# Sheet1.net
KiCad netlist of a schematic drawn in Altium Designer
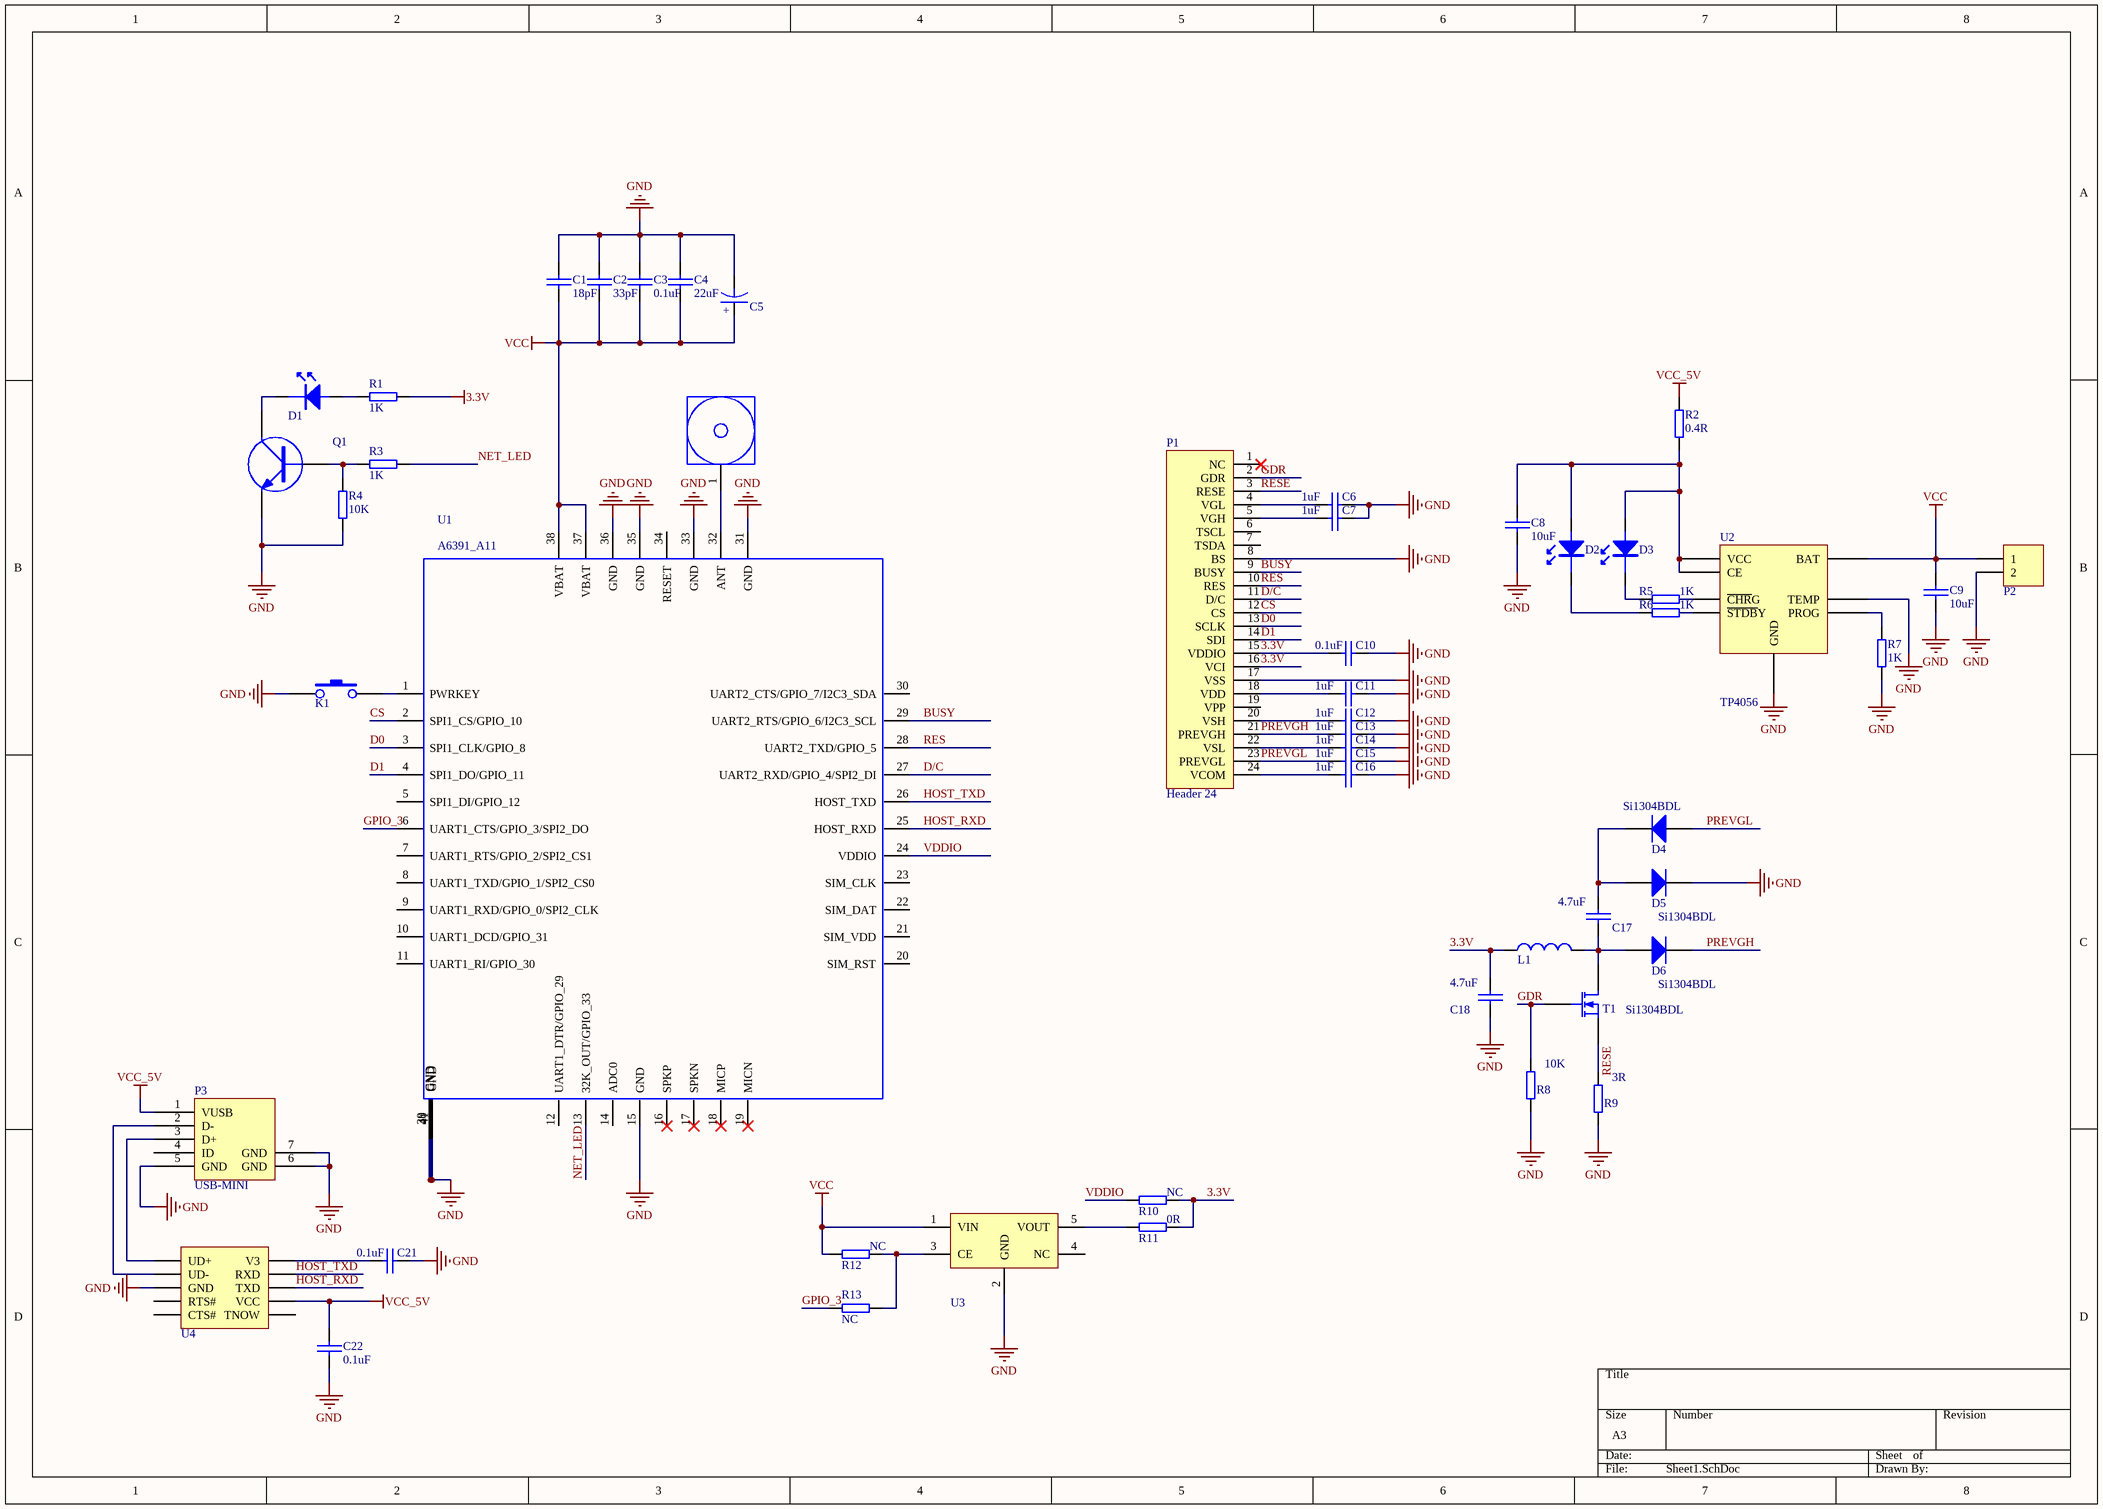
[diagram p0: Sheet1.SchDoc]

(export (version "E")
  (design (tool "Eeschema 10.0.6"))
  (components
    (comp (ref "ANTENNA")
      (value "ANTENNA")
      (footprint "GSM/GPRS/3G弹簧天线")
      (libsource (lib "Library") (part "ANTENNA"))
    )
    (comp (ref "C1")
      (value "18pF")
      (footprint "0603C-Cap")
      (description "ceramics")
      (libsource (lib "Library") (part "Cap"))
    )
    (comp (ref "C2")
      (value "33pF")
      (footprint "0603C-Cap")
      (description "ceramics")
      (libsource (lib "Library") (part "Cap"))
    )
    (comp (ref "C3")
      (value "0.1uF")
      (footprint "0603C-Cap")
      (description "ceramics")
      (libsource (lib "Library") (part "Cap"))
    )
    (comp (ref "C4")
      (value "22uF")
      (footprint "0603C-Cap")
      (description "ceramics")
      (libsource (lib "Library") (part "Cap"))
    )
    (comp (ref "C5")
      (value "Cap_C")
      (footprint "CAPM-B-3528X21N")
      (description "Electrolytic")
      (libsource (lib "Library") (part "Cap_C"))
    )
    (comp (ref "C6")
      (value "1uF")
      (footprint "0603C-Cap")
      (description "ceramics")
      (libsource (lib "Library") (part "Cap"))
    )
    (comp (ref "C7")
      (value "1uF")
      (footprint "0603C-Cap")
      (description "ceramics")
      (libsource (lib "Library") (part "Cap"))
    )
    (comp (ref "C8")
      (value "10uF")
      (footprint "0603C-Cap")
      (description "ceramics")
      (libsource (lib "Library") (part "Cap"))
    )
    (comp (ref "C9")
      (value "10uF")
      (footprint "0603C-Cap")
      (description "ceramics")
      (libsource (lib "Library") (part "Cap"))
    )
    (comp (ref "C10")
      (value "0.1uF")
      (footprint "0603C-Cap")
      (description "ceramics")
      (libsource (lib "Library") (part "Cap"))
    )
    (comp (ref "C11")
      (value "1uF")
      (footprint "0603C-Cap")
      (description "ceramics")
      (libsource (lib "Library") (part "Cap"))
    )
    (comp (ref "C12")
      (value "1uF")
      (footprint "0603C-Cap")
      (description "ceramics")
      (libsource (lib "Library") (part "Cap"))
    )
    (comp (ref "C13")
      (value "1uF")
      (footprint "0603C-Cap")
      (description "ceramics")
      (libsource (lib "Library") (part "Cap"))
    )
    (comp (ref "C14")
      (value "1uF")
      (footprint "0603C-Cap")
      (description "ceramics")
      (libsource (lib "Library") (part "Cap"))
    )
    (comp (ref "C15")
      (value "1uF")
      (footprint "0603C-Cap")
      (description "ceramics")
      (libsource (lib "Library") (part "Cap"))
    )
    (comp (ref "C16")
      (value "1uF")
      (footprint "0603C-Cap")
      (description "ceramics")
      (libsource (lib "Library") (part "Cap"))
    )
    (comp (ref "C17")
      (value "4.7uF")
      (footprint "0603C-Cap")
      (description "ceramics")
      (libsource (lib "Library") (part "Cap"))
    )
    (comp (ref "C18")
      (value "4.7uF")
      (footprint "0603C-Cap")
      (description "ceramics")
      (libsource (lib "Library") (part "Cap"))
    )
    (comp (ref "C21")
      (value "0.1uF")
      (footprint "0603C-Cap")
      (description "ceramics")
      (libsource (lib "Library") (part "Cap"))
    )
    (comp (ref "C22")
      (value "0.1uF")
      (footprint "0603C-Cap")
      (description "ceramics")
      (libsource (lib "Library") (part "Cap"))
    )
    (comp (ref "D1")
      (value "LED")
      (footprint "LED0603_B")
      (description "发光二极管")
      (libsource (lib "Library") (part "LED"))
    )
    (comp (ref "D2")
      (value "LED")
      (footprint "LED0603_B")
      (description "发光二极管")
      (libsource (lib "Library") (part "LED"))
    )
    (comp (ref "D3")
      (value "LED")
      (footprint "LED0603_B")
      (description "发光二极管")
      (libsource (lib "Library") (part "LED"))
    )
    (comp (ref "D4")
      (value "Si1304BDL")
      (footprint "SOD323")
      (libsource (lib "Library") (part "Diode BAS16"))
    )
    (comp (ref "D5")
      (value "Si1304BDL")
      (footprint "SOD323")
      (libsource (lib "Library") (part "Diode BAS16"))
    )
    (comp (ref "D6")
      (value "Si1304BDL")
      (footprint "SOD323")
      (libsource (lib "Library") (part "Diode BAS16"))
    )
    (comp (ref "K1") (value "SW_PB2") (footprint "KEY_4*4") (libsource (lib "Library") (part "SW_PB2")))
    (comp (ref "L1")
      (value "10uH")
      (footprint "3225 - duplicate")
      (description "INDUCTOR")
      (libsource (lib "Library") (part "Inductor"))
    )
    (comp (ref "P1")
      (value "Header 24")
      (footprint "FH12-24S-0.5SH")
      (description "Header, 7-Pin")
      (libsource (lib "Library") (part "Header 24"))
    )
    (comp (ref "P2") (value "Header 2") (footprint "2PIN") (libsource (lib "Library") (part "Header 2")))
    (comp (ref "P3")
      (value "USB-MINI")
      (footprint "Micro USB")
      (description "MINUSB")
      (libsource (lib "Library") (part "USB-MINI"))
    )
    (comp (ref "Q1")
      (value "8050")
      (footprint "SOT-23")
      (description "NPN")
      (libsource (lib "Library") (part "NPN"))
    )
    (comp (ref "R1")
      (value "1K")
      (footprint "0603C-Res")
      (description "电阻")
      (libsource (lib "Library") (part "RES"))
    )
    (comp (ref "R2")
      (value "0.4R")
      (footprint "0603C-Res")
      (description "电阻")
      (libsource (lib "Library") (part "RES"))
    )
    (comp (ref "R3")
      (value "1K")
      (footprint "0603C-Res")
      (description "电阻")
      (libsource (lib "Library") (part "RES"))
    )
    (comp (ref "R4")
      (value "10K")
      (footprint "0603C-Res")
      (description "电阻")
      (libsource (lib "Library") (part "RES"))
    )
    (comp (ref "R5")
      (value "1K")
      (footprint "0603C-Res")
      (description "电阻")
      (libsource (lib "Library") (part "RES"))
    )
    (comp (ref "R6")
      (value "1K")
      (footprint "0603C-Res")
      (description "电阻")
      (libsource (lib "Library") (part "RES"))
    )
    (comp (ref "R7")
      (value "1K")
      (footprint "0603C-Res")
      (description "电阻")
      (libsource (lib "Library") (part "RES"))
    )
    (comp (ref "R8")
      (value "10K")
      (footprint "0603C-Res")
      (description "电阻")
      (libsource (lib "Library") (part "RES"))
    )
    (comp (ref "R9")
      (value "3R")
      (footprint "0603C-Res")
      (description "电阻")
      (libsource (lib "Library") (part "RES"))
    )
    (comp (ref "R10")
      (value "NC")
      (footprint "0603C-Res")
      (description "电阻")
      (libsource (lib "Library") (part "RES"))
    )
    (comp (ref "R11")
      (value "0R")
      (footprint "0603C-Res")
      (description "电阻")
      (libsource (lib "Library") (part "RES"))
    )
    (comp (ref "R12")
      (value "NC")
      (footprint "0603C-Res")
      (description "电阻")
      (libsource (lib "Library") (part "RES"))
    )
    (comp (ref "R13")
      (value "NC")
      (footprint "0603C-Res")
      (description "电阻")
      (libsource (lib "Library") (part "RES"))
    )
    (comp (ref "T1") (value "Si1304BDL") (footprint "SOT-23") (libsource (lib "Library") (part "N_MOS")))
    (comp (ref "U1")
      (value "A6391_A11")
      (footprint "202")
      (description "202芯片")
      (libsource (lib "Library") (part "A6391_A11"))
    )
    (comp (ref "U2") (value "TP4056") (footprint "SOP8LM386") (libsource (lib "Library") (part "TP4056")))
    (comp (ref "U3")
      (value "ME6211C33")
      (footprint "SOT-23-5PIN")
      (libsource (lib "Library") (part "ME6211C33"))
    )
    (comp (ref "U4")
      (value "CH340E")
      (footprint "TSSOP50P490X110-10N")
      (libsource (lib "Library") (part "CH340E"))
    )
  )
  (nets
    (net (code "1") (name "/BUSY") (class "Default")
      (node (ref "P1") (pin "9") (pinfunction "BUSY_9") (pintype "passive"))
      (node (ref "U1") (pin "29") (pinfunction "UART2_RTS/GPIO_6/I2C3_SCL_29") (pintype "passive"))
    )
    (net (code "2") (name "/CS") (class "Default")
      (node (ref "P1") (pin "12") (pinfunction "CS_12") (pintype "passive"))
      (node (ref "U1") (pin "2") (pinfunction "SPI1_CS/GPIO_10_2") (pintype "passive"))
    )
    (net (code "3") (name "/D0") (class "Default")
      (node (ref "P1") (pin "13") (pinfunction "SCLK_13") (pintype "passive"))
      (node (ref "U1") (pin "3") (pinfunction "SPI1_CLK/GPIO_8_3") (pintype "passive"))
    )
    (net (code "4") (name "/D1") (class "Default")
      (node (ref "P1") (pin "14") (pinfunction "SDI_14") (pintype "passive"))
      (node (ref "U1") (pin "4") (pinfunction "SPI1_DO/GPIO_11_4") (pintype "passive"))
    )
    (net (code "5") (name "/D{slash}C") (class "Default")
      (node (ref "P1") (pin "11") (pinfunction "D/C_11") (pintype "passive"))
      (node (ref "U1") (pin "27") (pinfunction "UART2_RXD/GPIO_4/SPI2_DI_27") (pintype "passive"))
    )
    (net (code "6") (name "/GDR") (class "Default")
      (node (ref "P1") (pin "2") (pinfunction "GDR_2") (pintype "passive"))
      (node (ref "R8") (pin "2") (pinfunction "2_2") (pintype "passive"))
      (node (ref "T1") (pin "1") (pinfunction "G_1") (pintype "passive"))
    )
    (net (code "7") (name "/GPIO_3") (class "Default")
      (node (ref "R13") (pin "2") (pinfunction "2_2") (pintype "passive"))
      (node (ref "U1") (pin "6") (pinfunction "UART1_CTS/GPIO_3/SPI2_DO_6") (pintype "passive"))
    )
    (net (code "8") (name "/HOST_RXD") (class "Default")
      (node (ref "U1") (pin "25") (pinfunction "HOST_RXD_25") (pintype "passive"))
      (node (ref "U4") (pin "8") (pinfunction "TXD_8") (pintype "passive"))
    )
    (net (code "9") (name "/HOST_TXD") (class "Default")
      (node (ref "U1") (pin "26") (pinfunction "HOST_TXD_26") (pintype "passive"))
      (node (ref "U4") (pin "9") (pinfunction "RXD_9") (pintype "passive"))
    )
    (net (code "10") (name "/NET_LED") (class "Default")
      (node (ref "R3") (pin "1") (pinfunction "1_1") (pintype "passive"))
      (node (ref "U1") (pin "13") (pinfunction "32K_OUT/GPIO_33_13") (pintype "passive"))
    )
    (net (code "11") (name "/PREVGH") (class "Default")
      (node (ref "C13") (pin "2") (pinfunction "2_2") (pintype "passive"))
      (node (ref "D6") (pin "2") (pinfunction "K_2") (pintype "passive"))
      (node (ref "P1") (pin "21") (pinfunction "PREVGH_21") (pintype "passive"))
    )
    (net (code "12") (name "/PREVGL") (class "Default")
      (node (ref "C15") (pin "2") (pinfunction "2_2") (pintype "passive"))
      (node (ref "D4") (pin "1") (pinfunction "A_1") (pintype "passive"))
      (node (ref "P1") (pin "23") (pinfunction "PREVGL_23") (pintype "passive"))
    )
    (net (code "13") (name "/RES") (class "Default")
      (node (ref "P1") (pin "10") (pinfunction "RES_10") (pintype "passive"))
      (node (ref "U1") (pin "28") (pinfunction "UART2_TXD/GPIO_5_28") (pintype "passive"))
    )
    (net (code "14") (name "/RESE") (class "Default")
      (node (ref "P1") (pin "3") (pinfunction "RESE_3") (pintype "passive"))
      (node (ref "R9") (pin "2") (pinfunction "2_2") (pintype "passive"))
      (node (ref "T1") (pin "2") (pinfunction "S_2") (pintype "passive"))
    )
    (net (code "15") (name "/VDDIO") (class "Default")
      (node (ref "R10") (pin "1") (pinfunction "1_1") (pintype "passive"))
      (node (ref "U1") (pin "24") (pinfunction "VDDIO_24") (pintype "passive"))
    )
    (net (code "16") (name "3.3V") (class "Default")
      (node (ref "C10") (pin "2") (pinfunction "2_2") (pintype "passive"))
      (node (ref "C18") (pin "2") (pinfunction "2_2") (pintype "passive"))
      (node (ref "L1") (pin "1") (pinfunction "1_1") (pintype "passive"))
      (node (ref "P1") (pin "15") (pinfunction "VDDIO_15") (pintype "passive"))
      (node (ref "P1") (pin "16") (pinfunction "VCI_16") (pintype "passive"))
      (node (ref "R1") (pin "2") (pinfunction "2_2") (pintype "passive"))
      (node (ref "R10") (pin "2") (pinfunction "2_2") (pintype "passive"))
      (node (ref "R11") (pin "2") (pinfunction "2_2") (pintype "passive"))
    )
    (net (code "17") (name "GND") (class "Default")
      (node (ref "C1") (pin "1") (pinfunction "1_1") (pintype "passive"))
      (node (ref "C10") (pin "1") (pinfunction "1_1") (pintype "passive"))
      (node (ref "C11") (pin "1") (pinfunction "1_1") (pintype "passive"))
      (node (ref "C12") (pin "1") (pinfunction "1_1") (pintype "passive"))
      (node (ref "C13") (pin "1") (pinfunction "1_1") (pintype "passive"))
      (node (ref "C14") (pin "1") (pinfunction "1_1") (pintype "passive"))
      (node (ref "C15") (pin "1") (pinfunction "1_1") (pintype "passive"))
      (node (ref "C16") (pin "1") (pinfunction "1_1") (pintype "passive"))
      (node (ref "C18") (pin "1") (pinfunction "1_1") (pintype "passive"))
      (node (ref "C2") (pin "1") (pinfunction "1_1") (pintype "passive"))
      (node (ref "C21") (pin "1") (pinfunction "1_1") (pintype "passive"))
      (node (ref "C22") (pin "1") (pinfunction "1_1") (pintype "passive"))
      (node (ref "C3") (pin "1") (pinfunction "1_1") (pintype "passive"))
      (node (ref "C4") (pin "1") (pinfunction "1_1") (pintype "passive"))
      (node (ref "C5") (pin "2") (pinfunction "2_2") (pintype "passive"))
      (node (ref "C6") (pin "1") (pinfunction "1_1") (pintype "passive"))
      (node (ref "C7") (pin "1") (pinfunction "1_1") (pintype "passive"))
      (node (ref "C8") (pin "2") (pinfunction "2_2") (pintype "passive"))
      (node (ref "C9") (pin "2") (pinfunction "2_2") (pintype "passive"))
      (node (ref "D5") (pin "2") (pinfunction "K_2") (pintype "passive"))
      (node (ref "K1") (pin "1") (pinfunction "1_1") (pintype "passive"))
      (node (ref "P1") (pin "17") (pinfunction "VSS_17") (pintype "passive"))
      (node (ref "P1") (pin "8") (pinfunction "BS_8") (pintype "passive"))
      (node (ref "P2") (pin "2") (pinfunction "2_2") (pintype "passive"))
      (node (ref "P3") (pin "5") (pinfunction "GND_5") (pintype "passive"))
      (node (ref "P3") (pin "6") (pinfunction "GND_6") (pintype "passive"))
      (node (ref "P3") (pin "7") (pinfunction "GND_7") (pintype "passive"))
      (node (ref "Q1") (pin "2") (pinfunction "E_2") (pintype "passive"))
      (node (ref "R4") (pin "1") (pinfunction "1_1") (pintype "passive"))
      (node (ref "R7") (pin "2") (pinfunction "2_2") (pintype "passive"))
      (node (ref "R8") (pin "1") (pinfunction "1_1") (pintype "passive"))
      (node (ref "R9") (pin "1") (pinfunction "1_1") (pintype "passive"))
      (node (ref "U1") (pin "15") (pinfunction "GND_15") (pintype "passive"))
      (node (ref "U1") (pin "31") (pinfunction "GND_31") (pintype "passive"))
      (node (ref "U1") (pin "33") (pinfunction "GND_33") (pintype "passive"))
      (node (ref "U1") (pin "35") (pinfunction "GND_35") (pintype "passive"))
      (node (ref "U1") (pin "36") (pinfunction "GND_36") (pintype "passive"))
      (node (ref "U1") (pin "39") (pinfunction "GND_39") (pintype "power_in"))
      (node (ref "U1") (pin "40") (pinfunction "GND_40") (pintype "power_in"))
      (node (ref "U1") (pin "41") (pinfunction "GND_41") (pintype "power_in"))
      (node (ref "U2") (pin "1") (pinfunction "TEMP_1") (pintype "passive"))
      (node (ref "U2") (pin "3") (pinfunction "GND_3") (pintype "passive"))
      (node (ref "U3") (pin "2") (pinfunction "GND_2") (pintype "passive"))
      (node (ref "U4") (pin "3") (pinfunction "GND_3") (pintype "passive"))
    )
    (net (code "18") (name "Net-(D1-PadA)") (class "Default")
      (node (ref "D1") (pin "A") (pinfunction "A_A") (pintype "passive"))
      (node (ref "R1") (pin "1") (pinfunction "1_1") (pintype "passive"))
    )
    (net (code "19") (name "Net-(D2-PadK)") (class "Default")
      (node (ref "D2") (pin "K") (pinfunction "K_K") (pintype "passive"))
      (node (ref "R6") (pin "2") (pinfunction "2_2") (pintype "passive"))
    )
    (net (code "20") (name "Net-(D3-PadK)") (class "Default")
      (node (ref "D3") (pin "K") (pinfunction "K_K") (pintype "passive"))
      (node (ref "R5") (pin "2") (pinfunction "2_2") (pintype "passive"))
    )
    (net (code "21") (name "Net-(D4-K)") (class "Default")
      (node (ref "C17") (pin "2") (pinfunction "2_2") (pintype "passive"))
      (node (ref "D4") (pin "2") (pinfunction "K_2") (pintype "passive"))
      (node (ref "D5") (pin "1") (pinfunction "A_1") (pintype "passive"))
    )
    (net (code "22") (name "Net-(D6-A)") (class "Default")
      (node (ref "C17") (pin "1") (pinfunction "1_1") (pintype "passive"))
      (node (ref "D6") (pin "1") (pinfunction "A_1") (pintype "passive"))
      (node (ref "L1") (pin "2") (pinfunction "2_2") (pintype "passive"))
      (node (ref "T1") (pin "3") (pinfunction "D_3") (pintype "passive"))
    )
    (net (code "23") (name "Net-(P1-VCOM)") (class "Default")
      (node (ref "C16") (pin "2") (pinfunction "2_2") (pintype "passive"))
      (node (ref "P1") (pin "24") (pinfunction "VCOM_24") (pintype "passive"))
    )
    (net (code "24") (name "Net-(P1-VDD)") (class "Default")
      (node (ref "C11") (pin "2") (pinfunction "2_2") (pintype "passive"))
      (node (ref "P1") (pin "18") (pinfunction "VDD_18") (pintype "passive"))
    )
    (net (code "25") (name "Net-(P1-VGH)") (class "Default")
      (node (ref "C7") (pin "2") (pinfunction "2_2") (pintype "passive"))
      (node (ref "P1") (pin "5") (pinfunction "VGH_5") (pintype "passive"))
    )
    (net (code "26") (name "Net-(P1-VGL)") (class "Default")
      (node (ref "C6") (pin "2") (pinfunction "2_2") (pintype "passive"))
      (node (ref "P1") (pin "4") (pinfunction "VGL_4") (pintype "passive"))
    )
    (net (code "27") (name "Net-(P1-VSH)") (class "Default")
      (node (ref "C12") (pin "2") (pinfunction "2_2") (pintype "passive"))
      (node (ref "P1") (pin "20") (pinfunction "VSH_20") (pintype "passive"))
    )
    (net (code "28") (name "Net-(P1-VSL)") (class "Default")
      (node (ref "C14") (pin "2") (pinfunction "2_2") (pintype "passive"))
      (node (ref "P1") (pin "22") (pinfunction "VSL_22") (pintype "passive"))
    )
    (net (code "29") (name "Net-(P3-D+)") (class "Default")
      (node (ref "P3") (pin "3") (pinfunction "D+_3") (pintype "passive"))
      (node (ref "U4") (pin "1") (pinfunction "UD+_1") (pintype "passive"))
    )
    (net (code "30") (name "Net-(P3-D-)") (class "Default")
      (node (ref "P3") (pin "2") (pinfunction "D-_2") (pintype "passive"))
      (node (ref "U4") (pin "2") (pinfunction "UD-_2") (pintype "passive"))
    )
    (net (code "31") (name "Net-(Q1-B)") (class "Default")
      (node (ref "Q1") (pin "1") (pinfunction "B_1") (pintype "passive"))
      (node (ref "R3") (pin "2") (pinfunction "2_2") (pintype "passive"))
      (node (ref "R4") (pin "2") (pinfunction "2_2") (pintype "passive"))
    )
    (net (code "32") (name "Net-(Q1-C)") (class "Default")
      (node (ref "D1") (pin "K") (pinfunction "K_K") (pintype "passive"))
      (node (ref "Q1") (pin "3") (pinfunction "C_3") (pintype "passive"))
    )
    (net (code "33") (name "Net-(U1-ANT)") (class "Default")
      (node (ref "ANTENNA") (pin "1") (pinfunction "1_1") (pintype "passive"))
      (node (ref "U1") (pin "32") (pinfunction "ANT_32") (pintype "passive"))
    )
    (net (code "34") (name "Net-(U1-PWRKEY)") (class "Default")
      (node (ref "K1") (pin "2") (pinfunction "2_2") (pintype "passive"))
      (node (ref "U1") (pin "1") (pinfunction "PWRKEY_1") (pintype "passive"))
    )
    (net (code "35") (name "Net-(U2-CE)") (class "Default")
      (node (ref "C8") (pin "1") (pinfunction "1_1") (pintype "passive"))
      (node (ref "D2") (pin "A") (pinfunction "A_A") (pintype "passive"))
      (node (ref "D3") (pin "A") (pinfunction "A_A") (pintype "passive"))
      (node (ref "R2") (pin "2") (pinfunction "2_2") (pintype "passive"))
      (node (ref "U2") (pin "4") (pinfunction "VCC_4") (pintype "passive"))
      (node (ref "U2") (pin "8") (pinfunction "CE_8") (pintype "passive"))
    )
    (net (code "36") (name "Net-(U2-PROG)") (class "Default")
      (node (ref "R7") (pin "1") (pinfunction "1_1") (pintype "passive"))
      (node (ref "U2") (pin "2") (pinfunction "PROG_2") (pintype "passive"))
    )
    (net (code "37") (name "Net-(U2-~{CHR}G)") (class "Default")
      (node (ref "R5") (pin "1") (pinfunction "1_1") (pintype "passive"))
      (node (ref "U2") (pin "7") (pinfunction "~{CHR}G_7") (pintype "passive"))
    )
    (net (code "38") (name "Net-(U2-~{STDB}Y)") (class "Default")
      (node (ref "R6") (pin "1") (pinfunction "1_1") (pintype "passive"))
      (node (ref "U2") (pin "6") (pinfunction "~{STDB}Y_6") (pintype "passive"))
    )
    (net (code "39") (name "Net-(U3-CE)") (class "Default")
      (node (ref "R12") (pin "2") (pinfunction "2_2") (pintype "passive"))
      (node (ref "R13") (pin "1") (pinfunction "1_1") (pintype "passive"))
      (node (ref "U3") (pin "3") (pinfunction "CE_3") (pintype "passive"))
    )
    (net (code "40") (name "Net-(U3-VOUT)") (class "Default")
      (node (ref "R11") (pin "1") (pinfunction "1_1") (pintype "passive"))
      (node (ref "U3") (pin "5") (pinfunction "VOUT_5") (pintype "passive"))
    )
    (net (code "41") (name "Net-(U4-V3)") (class "Default")
      (node (ref "C21") (pin "2") (pinfunction "2_2") (pintype "passive"))
      (node (ref "U4") (pin "10") (pinfunction "V3_10") (pintype "passive"))
    )
    (net (code "42") (name "VCC") (class "Default")
      (node (ref "C1") (pin "2") (pinfunction "2_2") (pintype "passive"))
      (node (ref "C2") (pin "2") (pinfunction "2_2") (pintype "passive"))
      (node (ref "C3") (pin "2") (pinfunction "2_2") (pintype "passive"))
      (node (ref "C4") (pin "2") (pinfunction "2_2") (pintype "passive"))
      (node (ref "C5") (pin "1") (pinfunction "1_1") (pintype "passive"))
      (node (ref "C9") (pin "1") (pinfunction "1_1") (pintype "passive"))
      (node (ref "P2") (pin "1") (pinfunction "1_1") (pintype "passive"))
      (node (ref "R12") (pin "1") (pinfunction "1_1") (pintype "passive"))
      (node (ref "U1") (pin "37") (pinfunction "VBAT_37") (pintype "passive"))
      (node (ref "U1") (pin "38") (pinfunction "VBAT_38") (pintype "passive"))
      (node (ref "U2") (pin "5") (pinfunction "BAT_5") (pintype "passive"))
      (node (ref "U3") (pin "1") (pinfunction "VIN_1") (pintype "passive"))
    )
    (net (code "43") (name "VCC_5V") (class "Default")
      (node (ref "C22") (pin "2") (pinfunction "2_2") (pintype "passive"))
      (node (ref "P3") (pin "1") (pinfunction "VUSB_1") (pintype "passive"))
      (node (ref "R2") (pin "1") (pinfunction "1_1") (pintype "passive"))
      (node (ref "U4") (pin "7") (pinfunction "VCC_7") (pintype "passive"))
    )
    (net (code "44") (name "unconnected-(P1-NC-Pad1)") (class "Default")
      (node (ref "P1") (pin "1") (pinfunction "NC_1") (pintype "passive+no_connect"))
    )
    (net (code "45") (name "unconnected-(P1-TSCL-Pad6)") (class "Default")
      (node (ref "P1") (pin "6") (pinfunction "TSCL_6") (pintype "passive"))
    )
    (net (code "46") (name "unconnected-(P1-TSDA-Pad7)") (class "Default")
      (node (ref "P1") (pin "7") (pinfunction "TSDA_7") (pintype "passive"))
    )
    (net (code "47") (name "unconnected-(P1-VPP-Pad19)") (class "Default")
      (node (ref "P1") (pin "19") (pinfunction "VPP_19") (pintype "passive"))
    )
    (net (code "48") (name "unconnected-(P3-ID-Pad4)") (class "Default")
      (node (ref "P3") (pin "4") (pinfunction "ID_4") (pintype "passive"))
    )
    (net (code "49") (name "unconnected-(U1-ADC0-Pad14)") (class "Default")
      (node (ref "U1") (pin "14") (pinfunction "ADC0_14") (pintype "passive"))
    )
    (net (code "50") (name "unconnected-(U1-MICN-Pad19)") (class "Default")
      (node (ref "U1") (pin "19") (pinfunction "MICN_19") (pintype "passive+no_connect"))
    )
    (net (code "51") (name "unconnected-(U1-MICP-Pad18)") (class "Default")
      (node (ref "U1") (pin "18") (pinfunction "MICP_18") (pintype "passive+no_connect"))
    )
    (net (code "52") (name "unconnected-(U1-RESET-Pad34)") (class "Default")
      (node (ref "U1") (pin "34") (pinfunction "RESET_34") (pintype "passive"))
    )
    (net (code "53") (name "unconnected-(U1-SIM_CLK-Pad23)") (class "Default")
      (node (ref "U1") (pin "23") (pinfunction "SIM_CLK_23") (pintype "passive"))
    )
    (net (code "54") (name "unconnected-(U1-SIM_DAT-Pad22)") (class "Default")
      (node (ref "U1") (pin "22") (pinfunction "SIM_DAT_22") (pintype "passive"))
    )
    (net (code "55") (name "unconnected-(U1-SIM_RST-Pad20)") (class "Default")
      (node (ref "U1") (pin "20") (pinfunction "SIM_RST_20") (pintype "passive"))
    )
    (net (code "56") (name "unconnected-(U1-SIM_VDD-Pad21)") (class "Default")
      (node (ref "U1") (pin "21") (pinfunction "SIM_VDD_21") (pintype "passive"))
    )
    (net (code "57") (name "unconnected-(U1-SPI1_DI{slash}GPIO_12-Pad5)") (class "Default")
      (node (ref "U1") (pin "5") (pinfunction "SPI1_DI/GPIO_12_5") (pintype "passive"))
    )
    (net (code "58") (name "unconnected-(U1-SPKN-Pad17)") (class "Default")
      (node (ref "U1") (pin "17") (pinfunction "SPKN_17") (pintype "passive+no_connect"))
    )
    (net (code "59") (name "unconnected-(U1-SPKP-Pad16)") (class "Default")
      (node (ref "U1") (pin "16") (pinfunction "SPKP_16") (pintype "passive+no_connect"))
    )
    (net (code "60") (name "unconnected-(U1-UART1_DCD{slash}GPIO_31-Pad10)") (class "Default")
      (node (ref "U1") (pin "10") (pinfunction "UART1_DCD/GPIO_31_10") (pintype "passive"))
    )
    (net (code "61") (name "unconnected-(U1-UART1_DTR{slash}GPIO_29-Pad12)") (class "Default")
      (node (ref "U1") (pin "12") (pinfunction "UART1_DTR/GPIO_29_12") (pintype "passive"))
    )
    (net (code "62") (name "unconnected-(U1-UART1_RI{slash}GPIO_30-Pad11)") (class "Default")
      (node (ref "U1") (pin "11") (pinfunction "UART1_RI/GPIO_30_11") (pintype "passive"))
    )
    (net (code "63") (name "unconnected-(U1-UART1_RTS{slash}GPIO_2{slash}SPI2_CS1-Pad7)") (class "Default")
      (node (ref "U1") (pin "7") (pinfunction "UART1_RTS/GPIO_2/SPI2_CS1_7") (pintype "passive"))
    )
    (net (code "64") (name "unconnected-(U1-UART1_RXD{slash}GPIO_0{slash}SPI2_CLK-Pad9)") (class "Default")
      (node (ref "U1") (pin "9") (pinfunction "UART1_RXD/GPIO_0/SPI2_CLK_9") (pintype "passive"))
    )
    (net (code "65") (name "unconnected-(U1-UART1_TXD{slash}GPIO_1{slash}SPI2_CS0-Pad8)") (class "Default")
      (node (ref "U1") (pin "8") (pinfunction "UART1_TXD/GPIO_1/SPI2_CS0_8") (pintype "passive"))
    )
    (net (code "66") (name "unconnected-(U1-UART2_CTS{slash}GPIO_7{slash}I2C3_SDA-Pad30)") (class "Default")
      (node (ref "U1") (pin "30") (pinfunction "UART2_CTS/GPIO_7/I2C3_SDA_30") (pintype "passive"))
    )
    (net (code "67") (name "unconnected-(U3-NC-Pad4)") (class "Default")
      (node (ref "U3") (pin "4") (pinfunction "NC_4") (pintype "passive"))
    )
    (net (code "68") (name "unconnected-(U4-CTS#-Pad5)") (class "Default")
      (node (ref "U4") (pin "5") (pinfunction "CTS#_5") (pintype "passive"))
    )
    (net (code "69") (name "unconnected-(U4-RTS#-Pad4)") (class "Default")
      (node (ref "U4") (pin "4") (pinfunction "RTS#_4") (pintype "passive"))
    )
    (net (code "70") (name "unconnected-(U4-TNOW-Pad6)") (class "Default")
      (node (ref "U4") (pin "6") (pinfunction "TNOW_6") (pintype "passive"))
    )
  )
)
